# relay-attentuator-SMD.net
KiCad netlist of a schematic drawn in EAGLE
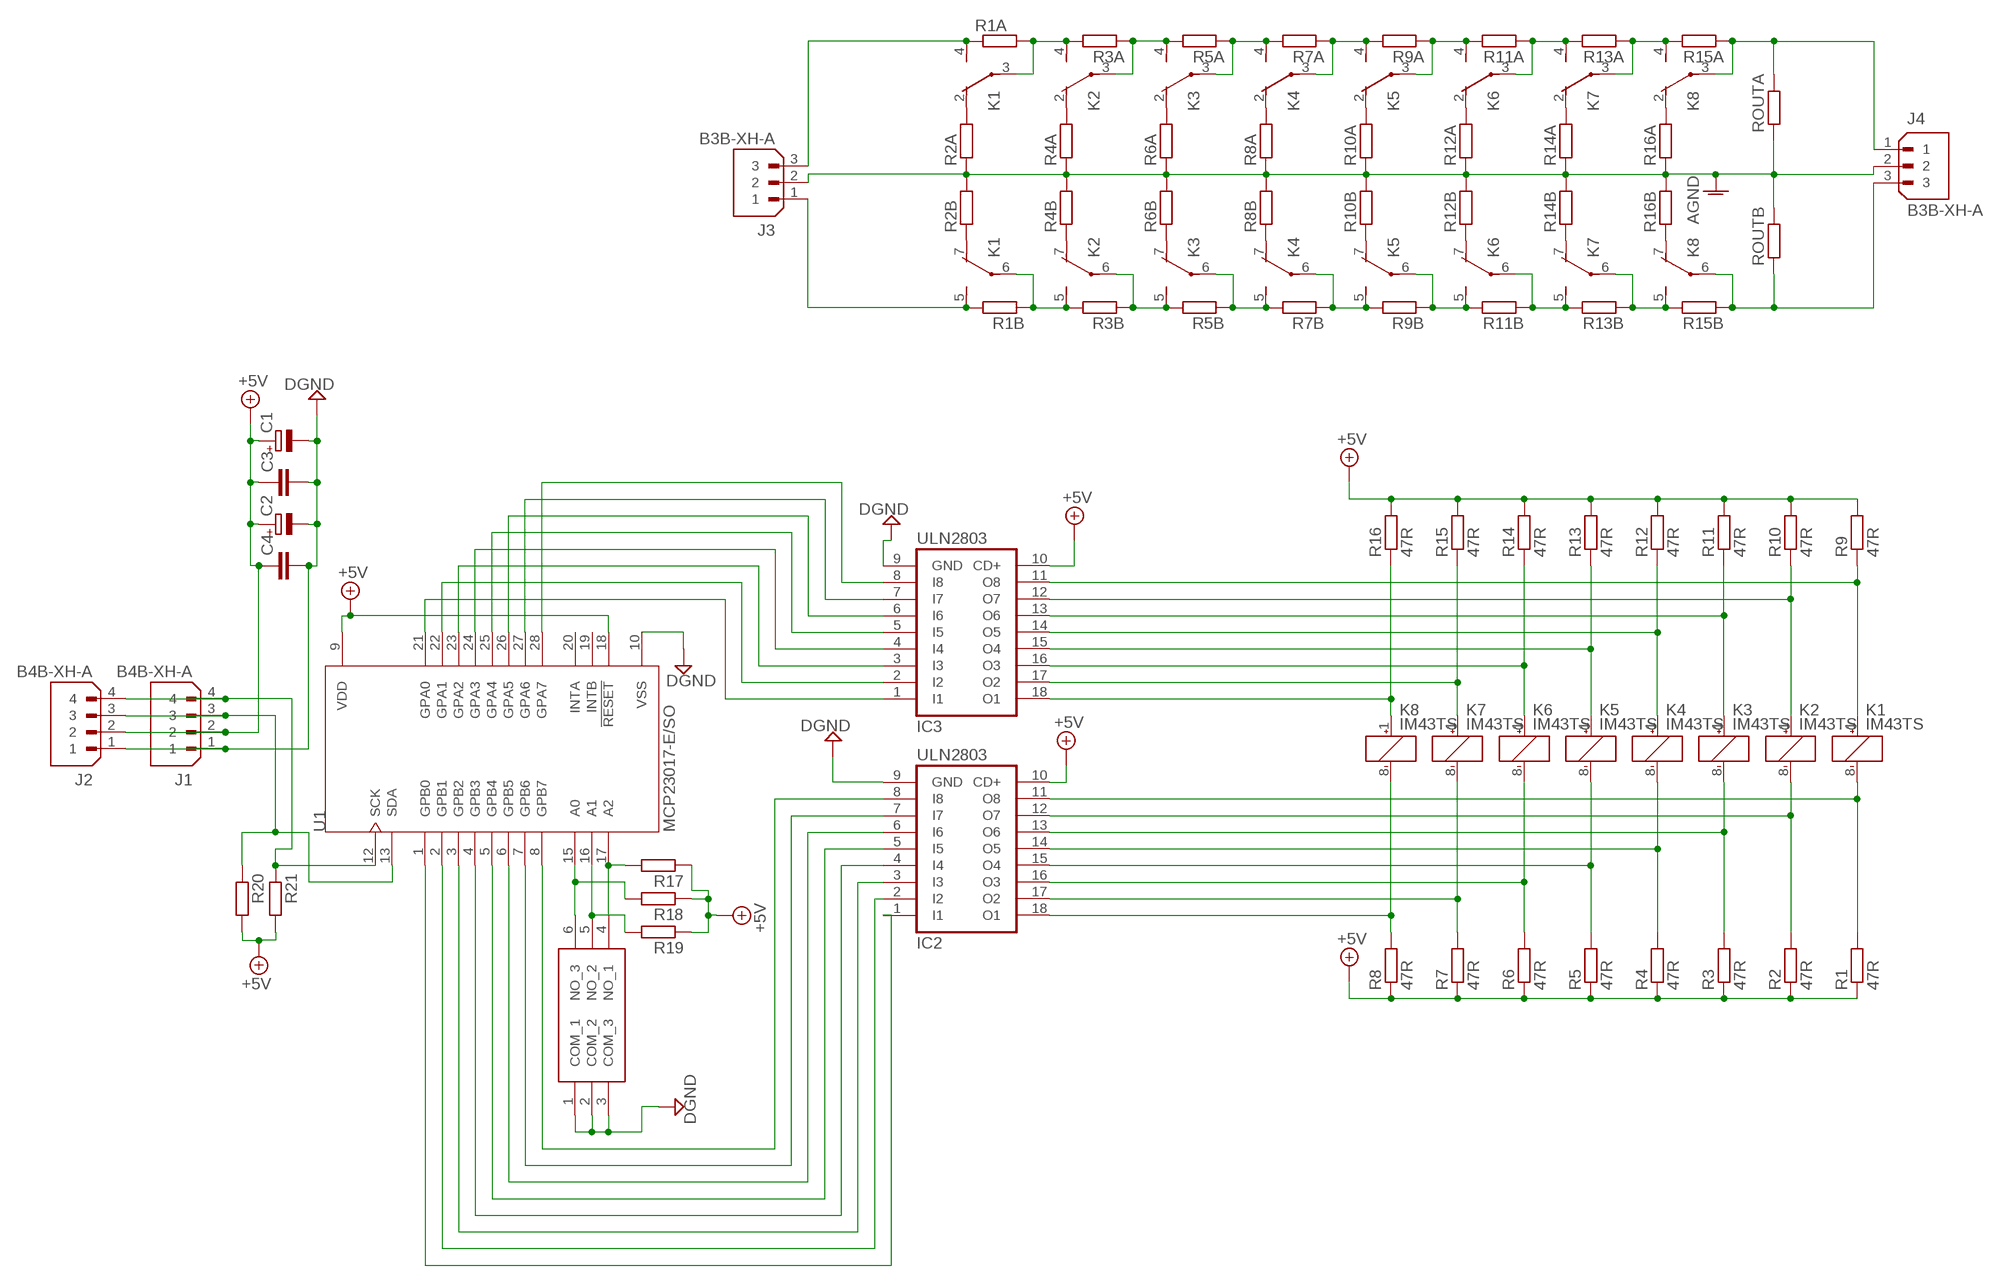
[diagram p0: schematic, sheet 1]

(export (version "E")
  (design (tool "Eeschema 10.0.6"))
  (components
    (comp (ref "C1")
      (value "CPOL-EUE3.5-8")
      (footprint "eagle-import:E3,5-8")
      (libsource (lib "eagle-import") (part "CPOL-EUE3.5-8"))
    )
    (comp (ref "C2")
      (value "CPOL-EUE3.5-8")
      (footprint "eagle-import:E3,5-8")
      (libsource (lib "eagle-import") (part "CPOL-EUE3.5-8"))
    )
    (comp (ref "C3")
      (value "C-EUC1206")
      (footprint "eagle-import:C1206")
      (libsource (lib "eagle-import") (part "C-EUC1206"))
    )
    (comp (ref "C4")
      (value "C-EUC1206")
      (footprint "eagle-import:C1206")
      (libsource (lib "eagle-import") (part "C-EUC1206"))
    )
    (comp (ref "IC2")
      (value "ULN2803")
      (footprint "eagle-import:SO-18W")
      (libsource (lib "eagle-import") (part "ULN2803ADW"))
    )
    (comp (ref "IC3")
      (value "ULN2803")
      (footprint "eagle-import:SO-18W")
      (libsource (lib "eagle-import") (part "ULN2803ADW"))
    )
    (comp (ref "J1")
      (value "B4B-XH-A")
      (footprint "eagle-import:JST_B4B-XH-A")
      (fields (field (name "MF") "JST Sales"))
      (libsource (lib "eagle-import") (part "B4B-XH-A"))
    )
    (comp (ref "J2")
      (value "B4B-XH-A")
      (footprint "eagle-import:JST_B4B-XH-A")
      (fields (field (name "MF") "JST Sales"))
      (libsource (lib "eagle-import") (part "B4B-XH-A"))
    )
    (comp (ref "J3")
      (value "B3B-XH-A")
      (footprint "eagle-import:JST_B3B-XH-A")
      (fields (field (name "MF") "JST Sales"))
      (libsource (lib "eagle-import") (part "B3B-XH-A"))
    )
    (comp (ref "J4")
      (value "B3B-XH-A")
      (footprint "eagle-import:JST_B3B-XH-A")
      (fields (field (name "MF") "JST Sales"))
      (libsource (lib "eagle-import") (part "B3B-XH-A"))
    )
    (comp (ref "K1")
      (value "IM43TS")
      (footprint "eagle-import:IM43TS")
      (libsource (lib "eagle-import") (part "IM43TS"))
    )
    (comp (ref "K2")
      (value "IM43TS")
      (footprint "eagle-import:IM43TS")
      (libsource (lib "eagle-import") (part "IM43TS"))
    )
    (comp (ref "K3")
      (value "IM43TS")
      (footprint "eagle-import:IM43TS")
      (libsource (lib "eagle-import") (part "IM43TS"))
    )
    (comp (ref "K4")
      (value "IM43TS")
      (footprint "eagle-import:IM43TS")
      (libsource (lib "eagle-import") (part "IM43TS"))
    )
    (comp (ref "K5")
      (value "IM43TS")
      (footprint "eagle-import:IM43TS")
      (libsource (lib "eagle-import") (part "IM43TS"))
    )
    (comp (ref "K6")
      (value "IM43TS")
      (footprint "eagle-import:IM43TS")
      (libsource (lib "eagle-import") (part "IM43TS"))
    )
    (comp (ref "K7")
      (value "IM43TS")
      (footprint "eagle-import:IM43TS")
      (libsource (lib "eagle-import") (part "IM43TS"))
    )
    (comp (ref "K8")
      (value "IM43TS")
      (footprint "eagle-import:IM43TS")
      (libsource (lib "eagle-import") (part "IM43TS"))
    )
    (comp (ref "R1")
      (value "47R")
      (footprint "eagle-import:R1206")
      (libsource (lib "eagle-import") (part "R-EU_R1206"))
    )
    (comp (ref "R1A")
      (value "R-EU_R1206")
      (footprint "eagle-import:R1206")
      (libsource (lib "eagle-import") (part "R-EU_R1206"))
    )
    (comp (ref "R1B")
      (value "R-EU_R1206")
      (footprint "eagle-import:R1206")
      (libsource (lib "eagle-import") (part "R-EU_R1206"))
    )
    (comp (ref "R2")
      (value "47R")
      (footprint "eagle-import:R1206")
      (libsource (lib "eagle-import") (part "R-EU_R1206"))
    )
    (comp (ref "R2A")
      (value "R-EU_R1206")
      (footprint "eagle-import:R1206")
      (libsource (lib "eagle-import") (part "R-EU_R1206"))
    )
    (comp (ref "R2B")
      (value "R-EU_R1206")
      (footprint "eagle-import:R1206")
      (libsource (lib "eagle-import") (part "R-EU_R1206"))
    )
    (comp (ref "R3")
      (value "47R")
      (footprint "eagle-import:R1206")
      (libsource (lib "eagle-import") (part "R-EU_R1206"))
    )
    (comp (ref "R3A")
      (value "R-EU_R1206")
      (footprint "eagle-import:R1206")
      (libsource (lib "eagle-import") (part "R-EU_R1206"))
    )
    (comp (ref "R3B")
      (value "R-EU_R1206")
      (footprint "eagle-import:R1206")
      (libsource (lib "eagle-import") (part "R-EU_R1206"))
    )
    (comp (ref "R4")
      (value "47R")
      (footprint "eagle-import:R1206")
      (libsource (lib "eagle-import") (part "R-EU_R1206"))
    )
    (comp (ref "R4A")
      (value "R-EU_R1206")
      (footprint "eagle-import:R1206")
      (libsource (lib "eagle-import") (part "R-EU_R1206"))
    )
    (comp (ref "R4B")
      (value "R-EU_R1206")
      (footprint "eagle-import:R1206")
      (libsource (lib "eagle-import") (part "R-EU_R1206"))
    )
    (comp (ref "R5")
      (value "47R")
      (footprint "eagle-import:R1206")
      (libsource (lib "eagle-import") (part "R-EU_R1206"))
    )
    (comp (ref "R5A")
      (value "R-EU_R1206")
      (footprint "eagle-import:R1206")
      (libsource (lib "eagle-import") (part "R-EU_R1206"))
    )
    (comp (ref "R5B")
      (value "R-EU_R1206")
      (footprint "eagle-import:R1206")
      (libsource (lib "eagle-import") (part "R-EU_R1206"))
    )
    (comp (ref "R6")
      (value "47R")
      (footprint "eagle-import:R1206")
      (libsource (lib "eagle-import") (part "R-EU_R1206"))
    )
    (comp (ref "R6A")
      (value "R-EU_R1206")
      (footprint "eagle-import:R1206")
      (libsource (lib "eagle-import") (part "R-EU_R1206"))
    )
    (comp (ref "R6B")
      (value "R-EU_R1206")
      (footprint "eagle-import:R1206")
      (libsource (lib "eagle-import") (part "R-EU_R1206"))
    )
    (comp (ref "R7")
      (value "47R")
      (footprint "eagle-import:R1206")
      (libsource (lib "eagle-import") (part "R-EU_R1206"))
    )
    (comp (ref "R7A")
      (value "R-EU_R1206")
      (footprint "eagle-import:R1206")
      (libsource (lib "eagle-import") (part "R-EU_R1206"))
    )
    (comp (ref "R7B")
      (value "R-EU_R1206")
      (footprint "eagle-import:R1206")
      (libsource (lib "eagle-import") (part "R-EU_R1206"))
    )
    (comp (ref "R8")
      (value "47R")
      (footprint "eagle-import:R1206")
      (libsource (lib "eagle-import") (part "R-EU_R1206"))
    )
    (comp (ref "R8A")
      (value "R-EU_R1206")
      (footprint "eagle-import:R1206")
      (libsource (lib "eagle-import") (part "R-EU_R1206"))
    )
    (comp (ref "R8B")
      (value "R-EU_R1206")
      (footprint "eagle-import:R1206")
      (libsource (lib "eagle-import") (part "R-EU_R1206"))
    )
    (comp (ref "R9")
      (value "47R")
      (footprint "eagle-import:R1206")
      (libsource (lib "eagle-import") (part "R-EU_R1206"))
    )
    (comp (ref "R9A")
      (value "R-EU_R1206")
      (footprint "eagle-import:R1206")
      (libsource (lib "eagle-import") (part "R-EU_R1206"))
    )
    (comp (ref "R9B")
      (value "R-EU_R1206")
      (footprint "eagle-import:R1206")
      (libsource (lib "eagle-import") (part "R-EU_R1206"))
    )
    (comp (ref "R10")
      (value "47R")
      (footprint "eagle-import:R1206")
      (libsource (lib "eagle-import") (part "R-EU_R1206"))
    )
    (comp (ref "R10A")
      (value "R-EU_R1206")
      (footprint "eagle-import:R1206")
      (libsource (lib "eagle-import") (part "R-EU_R1206"))
    )
    (comp (ref "R10B")
      (value "R-EU_R1206")
      (footprint "eagle-import:R1206")
      (libsource (lib "eagle-import") (part "R-EU_R1206"))
    )
    (comp (ref "R11")
      (value "47R")
      (footprint "eagle-import:R1206")
      (libsource (lib "eagle-import") (part "R-EU_R1206"))
    )
    (comp (ref "R11A")
      (value "R-EU_R1206")
      (footprint "eagle-import:R1206")
      (libsource (lib "eagle-import") (part "R-EU_R1206"))
    )
    (comp (ref "R11B")
      (value "R-EU_R1206")
      (footprint "eagle-import:R1206")
      (libsource (lib "eagle-import") (part "R-EU_R1206"))
    )
    (comp (ref "R12")
      (value "47R")
      (footprint "eagle-import:R1206")
      (libsource (lib "eagle-import") (part "R-EU_R1206"))
    )
    (comp (ref "R12A")
      (value "R-EU_R1206")
      (footprint "eagle-import:R1206")
      (libsource (lib "eagle-import") (part "R-EU_R1206"))
    )
    (comp (ref "R12B")
      (value "R-EU_R1206")
      (footprint "eagle-import:R1206")
      (libsource (lib "eagle-import") (part "R-EU_R1206"))
    )
    (comp (ref "R13")
      (value "47R")
      (footprint "eagle-import:R1206")
      (libsource (lib "eagle-import") (part "R-EU_R1206"))
    )
    (comp (ref "R13A")
      (value "R-EU_R1206")
      (footprint "eagle-import:R1206")
      (libsource (lib "eagle-import") (part "R-EU_R1206"))
    )
    (comp (ref "R13B")
      (value "R-EU_R1206")
      (footprint "eagle-import:R1206")
      (libsource (lib "eagle-import") (part "R-EU_R1206"))
    )
    (comp (ref "R14")
      (value "47R")
      (footprint "eagle-import:R1206")
      (libsource (lib "eagle-import") (part "R-EU_R1206"))
    )
    (comp (ref "R14A")
      (value "R-EU_R1206")
      (footprint "eagle-import:R1206")
      (libsource (lib "eagle-import") (part "R-EU_R1206"))
    )
    (comp (ref "R14B")
      (value "R-EU_R1206")
      (footprint "eagle-import:R1206")
      (libsource (lib "eagle-import") (part "R-EU_R1206"))
    )
    (comp (ref "R15")
      (value "47R")
      (footprint "eagle-import:R1206")
      (libsource (lib "eagle-import") (part "R-EU_R1206"))
    )
    (comp (ref "R15A")
      (value "R-EU_R1206")
      (footprint "eagle-import:R1206")
      (libsource (lib "eagle-import") (part "R-EU_R1206"))
    )
    (comp (ref "R15B")
      (value "R-EU_R1206")
      (footprint "eagle-import:R1206")
      (libsource (lib "eagle-import") (part "R-EU_R1206"))
    )
    (comp (ref "R16")
      (value "47R")
      (footprint "eagle-import:R1206")
      (libsource (lib "eagle-import") (part "R-EU_R1206"))
    )
    (comp (ref "R16A")
      (value "R-EU_R1206")
      (footprint "eagle-import:R1206")
      (libsource (lib "eagle-import") (part "R-EU_R1206"))
    )
    (comp (ref "R16B")
      (value "R-EU_R1206")
      (footprint "eagle-import:R1206")
      (libsource (lib "eagle-import") (part "R-EU_R1206"))
    )
    (comp (ref "R17")
      (value "47R")
      (footprint "eagle-import:R1206")
      (libsource (lib "eagle-import") (part "R-EU_R1206"))
    )
    (comp (ref "R18")
      (value "47R")
      (footprint "eagle-import:R1206")
      (libsource (lib "eagle-import") (part "R-EU_R1206"))
    )
    (comp (ref "R19")
      (value "47R")
      (footprint "eagle-import:R1206")
      (libsource (lib "eagle-import") (part "R-EU_R1206"))
    )
    (comp (ref "R20")
      (value "47R")
      (footprint "eagle-import:R1206")
      (libsource (lib "eagle-import") (part "R-EU_R1206"))
    )
    (comp (ref "R21")
      (value "47R")
      (footprint "eagle-import:R1206")
      (libsource (lib "eagle-import") (part "R-EU_R1206"))
    )
    (comp (ref "ROUTA")
      (value "R-EU_R1206")
      (footprint "eagle-import:R1206")
      (libsource (lib "eagle-import") (part "R-EU_R1206"))
    )
    (comp (ref "ROUTB")
      (value "R-EU_R1206")
      (footprint "eagle-import:R1206")
      (libsource (lib "eagle-import") (part "R-EU_R1206"))
    )
    (comp (ref "S1")
      (value "2454982-2")
      (footprint "eagle-import:24549822")
      (fields (field (name "MOUSER_PART_NUMBER") "655-2454982-2"))
      (libsource (lib "eagle-import") (part "2454982-2"))
    )
    (comp (ref "U1")
      (value "MCP23017-E/SO")
      (footprint "eagle-import:SOIC127P1030X265-28N")
      (fields (field (name "MF") "Microchip"))
      (libsource (lib "eagle-import") (part "MCP23017-E/SO"))
    )
  )
  (nets
    (net (code "1") (name "+5V") (class "Default")
      (node (ref "C1") (pin "+") (pinfunction "+_+") (pintype "passive"))
      (node (ref "C2") (pin "+") (pinfunction "+_+") (pintype "passive"))
      (node (ref "C3") (pin "1") (pinfunction "1_1") (pintype "passive"))
      (node (ref "C4") (pin "1") (pinfunction "1_1") (pintype "passive"))
      (node (ref "IC2") (pin "10") (pinfunction "CD+_10") (pintype "passive"))
      (node (ref "IC3") (pin "10") (pinfunction "CD+_10") (pintype "passive"))
      (node (ref "J1") (pin "2") (pinfunction "2_2") (pintype "passive"))
      (node (ref "J2") (pin "2") (pinfunction "2_2") (pintype "passive"))
      (node (ref "R1") (pin "1") (pinfunction "1_1") (pintype "passive"))
      (node (ref "R10") (pin "2") (pinfunction "2_2") (pintype "passive"))
      (node (ref "R11") (pin "2") (pinfunction "2_2") (pintype "passive"))
      (node (ref "R12") (pin "2") (pinfunction "2_2") (pintype "passive"))
      (node (ref "R13") (pin "2") (pinfunction "2_2") (pintype "passive"))
      (node (ref "R14") (pin "2") (pinfunction "2_2") (pintype "passive"))
      (node (ref "R15") (pin "2") (pinfunction "2_2") (pintype "passive"))
      (node (ref "R16") (pin "2") (pinfunction "2_2") (pintype "passive"))
      (node (ref "R17") (pin "1") (pinfunction "1_1") (pintype "passive"))
      (node (ref "R18") (pin "1") (pinfunction "1_1") (pintype "passive"))
      (node (ref "R19") (pin "1") (pinfunction "1_1") (pintype "passive"))
      (node (ref "R2") (pin "1") (pinfunction "1_1") (pintype "passive"))
      (node (ref "R20") (pin "2") (pinfunction "2_2") (pintype "passive"))
      (node (ref "R21") (pin "2") (pinfunction "2_2") (pintype "passive"))
      (node (ref "R3") (pin "1") (pinfunction "1_1") (pintype "passive"))
      (node (ref "R4") (pin "1") (pinfunction "1_1") (pintype "passive"))
      (node (ref "R5") (pin "1") (pinfunction "1_1") (pintype "passive"))
      (node (ref "R6") (pin "1") (pinfunction "1_1") (pintype "passive"))
      (node (ref "R7") (pin "1") (pinfunction "1_1") (pintype "passive"))
      (node (ref "R8") (pin "1") (pinfunction "1_1") (pintype "passive"))
      (node (ref "R9") (pin "2") (pinfunction "2_2") (pintype "passive"))
      (node (ref "U1") (pin "18") (pinfunction "~{RESET}_18") (pintype "output"))
      (node (ref "U1") (pin "9") (pinfunction "VDD_9") (pintype "power_in"))
    )
    (net (code "2") (name "AGND") (class "Default")
      (node (ref "J3") (pin "2") (pinfunction "2_2") (pintype "passive"))
      (node (ref "J4") (pin "2") (pinfunction "2_2") (pintype "passive"))
      (node (ref "R10A") (pin "1") (pinfunction "1_1") (pintype "passive"))
      (node (ref "R10B") (pin "2") (pinfunction "2_2") (pintype "passive"))
      (node (ref "R12A") (pin "1") (pinfunction "1_1") (pintype "passive"))
      (node (ref "R12B") (pin "2") (pinfunction "2_2") (pintype "passive"))
      (node (ref "R14A") (pin "1") (pinfunction "1_1") (pintype "passive"))
      (node (ref "R14B") (pin "2") (pinfunction "2_2") (pintype "passive"))
      (node (ref "R16A") (pin "1") (pinfunction "1_1") (pintype "passive"))
      (node (ref "R16B") (pin "2") (pinfunction "2_2") (pintype "passive"))
      (node (ref "R2A") (pin "1") (pinfunction "1_1") (pintype "passive"))
      (node (ref "R2B") (pin "2") (pinfunction "2_2") (pintype "passive"))
      (node (ref "R4A") (pin "1") (pinfunction "1_1") (pintype "passive"))
      (node (ref "R4B") (pin "2") (pinfunction "2_2") (pintype "passive"))
      (node (ref "R6A") (pin "1") (pinfunction "1_1") (pintype "passive"))
      (node (ref "R6B") (pin "2") (pinfunction "2_2") (pintype "passive"))
      (node (ref "R8A") (pin "1") (pinfunction "1_1") (pintype "passive"))
      (node (ref "R8B") (pin "2") (pinfunction "2_2") (pintype "passive"))
      (node (ref "ROUTA") (pin "1") (pinfunction "1_1") (pintype "passive"))
      (node (ref "ROUTB") (pin "2") (pinfunction "2_2") (pintype "passive"))
    )
    (net (code "3") (name "DGND") (class "Default")
      (node (ref "C1") (pin "-") (pinfunction "-_-") (pintype "passive"))
      (node (ref "C2") (pin "-") (pinfunction "-_-") (pintype "passive"))
      (node (ref "C3") (pin "2") (pinfunction "2_2") (pintype "passive"))
      (node (ref "C4") (pin "2") (pinfunction "2_2") (pintype "passive"))
      (node (ref "IC2") (pin "9") (pinfunction "GND_9") (pintype "power_in"))
      (node (ref "IC3") (pin "9") (pinfunction "GND_9") (pintype "power_in"))
      (node (ref "J1") (pin "1") (pinfunction "1_1") (pintype "passive"))
      (node (ref "J2") (pin "1") (pinfunction "1_1") (pintype "passive"))
      (node (ref "S1") (pin "1") (pinfunction "COM_1_1") (pintype "bidirectional"))
      (node (ref "S1") (pin "2") (pinfunction "COM_2_2") (pintype "bidirectional"))
      (node (ref "S1") (pin "3") (pinfunction "COM_3_3") (pintype "bidirectional"))
      (node (ref "U1") (pin "10") (pinfunction "VSS_10") (pintype "power_in"))
    )
    (net (code "4") (name "Net-(IC2-I1)") (class "Default")
      (node (ref "IC2") (pin "1") (pinfunction "I1_1") (pintype "input"))
      (node (ref "U1") (pin "1") (pinfunction "GPB0_1") (pintype "bidirectional"))
    )
    (net (code "5") (name "Net-(IC2-I2)") (class "Default")
      (node (ref "IC2") (pin "2") (pinfunction "I2_2") (pintype "input"))
      (node (ref "U1") (pin "2") (pinfunction "GPB1_2") (pintype "bidirectional"))
    )
    (net (code "6") (name "Net-(IC2-I3)") (class "Default")
      (node (ref "IC2") (pin "3") (pinfunction "I3_3") (pintype "input"))
      (node (ref "U1") (pin "3") (pinfunction "GPB2_3") (pintype "bidirectional"))
    )
    (net (code "7") (name "Net-(IC2-I4)") (class "Default")
      (node (ref "IC2") (pin "4") (pinfunction "I4_4") (pintype "input"))
      (node (ref "U1") (pin "4") (pinfunction "GPB3_4") (pintype "bidirectional"))
    )
    (net (code "8") (name "Net-(IC2-I5)") (class "Default")
      (node (ref "IC2") (pin "5") (pinfunction "I5_5") (pintype "input"))
      (node (ref "U1") (pin "5") (pinfunction "GPB4_5") (pintype "bidirectional"))
    )
    (net (code "9") (name "Net-(IC2-I6)") (class "Default")
      (node (ref "IC2") (pin "6") (pinfunction "I6_6") (pintype "input"))
      (node (ref "U1") (pin "6") (pinfunction "GPB5_6") (pintype "bidirectional"))
    )
    (net (code "10") (name "Net-(IC2-I7)") (class "Default")
      (node (ref "IC2") (pin "7") (pinfunction "I7_7") (pintype "input"))
      (node (ref "U1") (pin "7") (pinfunction "GPB6_7") (pintype "bidirectional"))
    )
    (net (code "11") (name "Net-(IC2-I8)") (class "Default")
      (node (ref "IC2") (pin "8") (pinfunction "I8_8") (pintype "input"))
      (node (ref "U1") (pin "8") (pinfunction "GPB7_8") (pintype "bidirectional"))
    )
    (net (code "12") (name "Net-(IC2-O1)") (class "Default")
      (node (ref "IC2") (pin "18") (pinfunction "O1_18") (pintype "open_collector"))
      (node (ref "K8") (pin "8") (pinfunction "-_8") (pintype "passive"))
      (node (ref "R8") (pin "2") (pinfunction "2_2") (pintype "passive"))
    )
    (net (code "13") (name "Net-(IC2-O2)") (class "Default")
      (node (ref "IC2") (pin "17") (pinfunction "O2_17") (pintype "open_collector"))
      (node (ref "K7") (pin "8") (pinfunction "-_8") (pintype "passive"))
      (node (ref "R7") (pin "2") (pinfunction "2_2") (pintype "passive"))
    )
    (net (code "14") (name "Net-(IC2-O3)") (class "Default")
      (node (ref "IC2") (pin "16") (pinfunction "O3_16") (pintype "open_collector"))
      (node (ref "K6") (pin "8") (pinfunction "-_8") (pintype "passive"))
      (node (ref "R6") (pin "2") (pinfunction "2_2") (pintype "passive"))
    )
    (net (code "15") (name "Net-(IC2-O4)") (class "Default")
      (node (ref "IC2") (pin "15") (pinfunction "O4_15") (pintype "open_collector"))
      (node (ref "K5") (pin "8") (pinfunction "-_8") (pintype "passive"))
      (node (ref "R5") (pin "2") (pinfunction "2_2") (pintype "passive"))
    )
    (net (code "16") (name "Net-(IC2-O5)") (class "Default")
      (node (ref "IC2") (pin "14") (pinfunction "O5_14") (pintype "open_collector"))
      (node (ref "K4") (pin "8") (pinfunction "-_8") (pintype "passive"))
      (node (ref "R4") (pin "2") (pinfunction "2_2") (pintype "passive"))
    )
    (net (code "17") (name "Net-(IC2-O6)") (class "Default")
      (node (ref "IC2") (pin "13") (pinfunction "O6_13") (pintype "open_collector"))
      (node (ref "K3") (pin "8") (pinfunction "-_8") (pintype "passive"))
      (node (ref "R3") (pin "2") (pinfunction "2_2") (pintype "passive"))
    )
    (net (code "18") (name "Net-(IC2-O7)") (class "Default")
      (node (ref "IC2") (pin "12") (pinfunction "O7_12") (pintype "open_collector"))
      (node (ref "K2") (pin "8") (pinfunction "-_8") (pintype "passive"))
      (node (ref "R2") (pin "2") (pinfunction "2_2") (pintype "passive"))
    )
    (net (code "19") (name "Net-(IC2-O8)") (class "Default")
      (node (ref "IC2") (pin "11") (pinfunction "O8_11") (pintype "open_collector"))
      (node (ref "K1") (pin "8") (pinfunction "-_8") (pintype "passive"))
      (node (ref "R1") (pin "2") (pinfunction "2_2") (pintype "passive"))
    )
    (net (code "20") (name "Net-(IC3-I1)") (class "Default")
      (node (ref "IC3") (pin "1") (pinfunction "I1_1") (pintype "input"))
      (node (ref "U1") (pin "21") (pinfunction "GPA0_21") (pintype "bidirectional"))
    )
    (net (code "21") (name "Net-(IC3-I2)") (class "Default")
      (node (ref "IC3") (pin "2") (pinfunction "I2_2") (pintype "input"))
      (node (ref "U1") (pin "22") (pinfunction "GPA1_22") (pintype "bidirectional"))
    )
    (net (code "22") (name "Net-(IC3-I3)") (class "Default")
      (node (ref "IC3") (pin "3") (pinfunction "I3_3") (pintype "input"))
      (node (ref "U1") (pin "23") (pinfunction "GPA2_23") (pintype "bidirectional"))
    )
    (net (code "23") (name "Net-(IC3-I4)") (class "Default")
      (node (ref "IC3") (pin "4") (pinfunction "I4_4") (pintype "input"))
      (node (ref "U1") (pin "24") (pinfunction "GPA3_24") (pintype "bidirectional"))
    )
    (net (code "24") (name "Net-(IC3-I5)") (class "Default")
      (node (ref "IC3") (pin "5") (pinfunction "I5_5") (pintype "input"))
      (node (ref "U1") (pin "25") (pinfunction "GPA4_25") (pintype "bidirectional"))
    )
    (net (code "25") (name "Net-(IC3-I6)") (class "Default")
      (node (ref "IC3") (pin "6") (pinfunction "I6_6") (pintype "input"))
      (node (ref "U1") (pin "26") (pinfunction "GPA5_26") (pintype "bidirectional"))
    )
    (net (code "26") (name "Net-(IC3-I7)") (class "Default")
      (node (ref "IC3") (pin "7") (pinfunction "I7_7") (pintype "input"))
      (node (ref "U1") (pin "27") (pinfunction "GPA6_27") (pintype "bidirectional"))
    )
    (net (code "27") (name "Net-(IC3-I8)") (class "Default")
      (node (ref "IC3") (pin "8") (pinfunction "I8_8") (pintype "input"))
      (node (ref "U1") (pin "28") (pinfunction "GPA7_28") (pintype "bidirectional"))
    )
    (net (code "28") (name "Net-(IC3-O1)") (class "Default")
      (node (ref "IC3") (pin "18") (pinfunction "O1_18") (pintype "open_collector"))
      (node (ref "K8") (pin "1") (pinfunction "+_1") (pintype "passive"))
      (node (ref "R16") (pin "1") (pinfunction "1_1") (pintype "passive"))
    )
    (net (code "29") (name "Net-(IC3-O2)") (class "Default")
      (node (ref "IC3") (pin "17") (pinfunction "O2_17") (pintype "open_collector"))
      (node (ref "K7") (pin "1") (pinfunction "+_1") (pintype "passive"))
      (node (ref "R15") (pin "1") (pinfunction "1_1") (pintype "passive"))
    )
    (net (code "30") (name "Net-(IC3-O3)") (class "Default")
      (node (ref "IC3") (pin "16") (pinfunction "O3_16") (pintype "open_collector"))
      (node (ref "K6") (pin "1") (pinfunction "+_1") (pintype "passive"))
      (node (ref "R14") (pin "1") (pinfunction "1_1") (pintype "passive"))
    )
    (net (code "31") (name "Net-(IC3-O4)") (class "Default")
      (node (ref "IC3") (pin "15") (pinfunction "O4_15") (pintype "open_collector"))
      (node (ref "K5") (pin "1") (pinfunction "+_1") (pintype "passive"))
      (node (ref "R13") (pin "1") (pinfunction "1_1") (pintype "passive"))
    )
    (net (code "32") (name "Net-(IC3-O5)") (class "Default")
      (node (ref "IC3") (pin "14") (pinfunction "O5_14") (pintype "open_collector"))
      (node (ref "K4") (pin "1") (pinfunction "+_1") (pintype "passive"))
      (node (ref "R12") (pin "1") (pinfunction "1_1") (pintype "passive"))
    )
    (net (code "33") (name "Net-(IC3-O6)") (class "Default")
      (node (ref "IC3") (pin "13") (pinfunction "O6_13") (pintype "open_collector"))
      (node (ref "K3") (pin "1") (pinfunction "+_1") (pintype "passive"))
      (node (ref "R11") (pin "1") (pinfunction "1_1") (pintype "passive"))
    )
    (net (code "34") (name "Net-(IC3-O7)") (class "Default")
      (node (ref "IC3") (pin "12") (pinfunction "O7_12") (pintype "open_collector"))
      (node (ref "K2") (pin "1") (pinfunction "+_1") (pintype "passive"))
      (node (ref "R10") (pin "1") (pinfunction "1_1") (pintype "passive"))
    )
    (net (code "35") (name "Net-(IC3-O8)") (class "Default")
      (node (ref "IC3") (pin "11") (pinfunction "O8_11") (pintype "open_collector"))
      (node (ref "K1") (pin "1") (pinfunction "+_1") (pintype "passive"))
      (node (ref "R9") (pin "1") (pinfunction "1_1") (pintype "passive"))
    )
    (net (code "36") (name "Net-(K1B-O)") (class "Default")
      (node (ref "K1") (pin "2") (pinfunction "O_2") (pintype "passive"))
      (node (ref "R2A") (pin "2") (pinfunction "2_2") (pintype "passive"))
    )
    (net (code "37") (name "Net-(K1B-P)") (class "Default")
      (node (ref "K1") (pin "3") (pinfunction "P_3") (pintype "passive"))
      (node (ref "K2") (pin "4") (pinfunction "S_4") (pintype "passive"))
      (node (ref "R1A") (pin "2") (pinfunction "2_2") (pintype "passive"))
      (node (ref "R3A") (pin "2") (pinfunction "2_2") (pintype "passive"))
    )
    (net (code "38") (name "Net-(K1B-S)") (class "Default")
      (node (ref "J3") (pin "3") (pinfunction "3_3") (pintype "passive"))
      (node (ref "K1") (pin "4") (pinfunction "S_4") (pintype "passive"))
      (node (ref "R1A") (pin "1") (pinfunction "1_1") (pintype "passive"))
    )
    (net (code "39") (name "Net-(K1C-O)") (class "Default")
      (node (ref "K1") (pin "7") (pinfunction "O_7") (pintype "passive"))
      (node (ref "R2B") (pin "1") (pinfunction "1_1") (pintype "passive"))
    )
    (net (code "40") (name "Net-(K1C-P)") (class "Default")
      (node (ref "K1") (pin "6") (pinfunction "P_6") (pintype "passive"))
      (node (ref "K2") (pin "5") (pinfunction "S_5") (pintype "passive"))
      (node (ref "R1B") (pin "1") (pinfunction "1_1") (pintype "passive"))
      (node (ref "R3B") (pin "2") (pinfunction "2_2") (pintype "passive"))
    )
    (net (code "41") (name "Net-(K1C-S)") (class "Default")
      (node (ref "J3") (pin "1") (pinfunction "1_1") (pintype "passive"))
      (node (ref "K1") (pin "5") (pinfunction "S_5") (pintype "passive"))
      (node (ref "R1B") (pin "2") (pinfunction "2_2") (pintype "passive"))
    )
    (net (code "42") (name "Net-(K2B-O)") (class "Default")
      (node (ref "K2") (pin "2") (pinfunction "O_2") (pintype "passive"))
      (node (ref "R4A") (pin "2") (pinfunction "2_2") (pintype "passive"))
    )
    (net (code "43") (name "Net-(K2B-P)") (class "Default")
      (node (ref "K2") (pin "3") (pinfunction "P_3") (pintype "passive"))
      (node (ref "K3") (pin "4") (pinfunction "S_4") (pintype "passive"))
      (node (ref "R3A") (pin "1") (pinfunction "1_1") (pintype "passive"))
      (node (ref "R5A") (pin "2") (pinfunction "2_2") (pintype "passive"))
    )
    (net (code "44") (name "Net-(K2C-O)") (class "Default")
      (node (ref "K2") (pin "7") (pinfunction "O_7") (pintype "passive"))
      (node (ref "R4B") (pin "1") (pinfunction "1_1") (pintype "passive"))
    )
    (net (code "45") (name "Net-(K2C-P)") (class "Default")
      (node (ref "K2") (pin "6") (pinfunction "P_6") (pintype "passive"))
      (node (ref "K3") (pin "5") (pinfunction "S_5") (pintype "passive"))
      (node (ref "R3B") (pin "1") (pinfunction "1_1") (pintype "passive"))
      (node (ref "R5B") (pin "2") (pinfunction "2_2") (pintype "passive"))
    )
    (net (code "46") (name "Net-(K3B-O)") (class "Default")
      (node (ref "K3") (pin "2") (pinfunction "O_2") (pintype "passive"))
      (node (ref "R6A") (pin "2") (pinfunction "2_2") (pintype "passive"))
    )
    (net (code "47") (name "Net-(K3B-P)") (class "Default")
      (node (ref "K3") (pin "3") (pinfunction "P_3") (pintype "passive"))
      (node (ref "K4") (pin "4") (pinfunction "S_4") (pintype "passive"))
      (node (ref "R5A") (pin "1") (pinfunction "1_1") (pintype "passive"))
      (node (ref "R7A") (pin "2") (pinfunction "2_2") (pintype "passive"))
    )
    (net (code "48") (name "Net-(K3C-O)") (class "Default")
      (node (ref "K3") (pin "7") (pinfunction "O_7") (pintype "passive"))
      (node (ref "R6B") (pin "1") (pinfunction "1_1") (pintype "passive"))
    )
    (net (code "49") (name "Net-(K3C-P)") (class "Default")
      (node (ref "K3") (pin "6") (pinfunction "P_6") (pintype "passive"))
      (node (ref "K4") (pin "5") (pinfunction "S_5") (pintype "passive"))
      (node (ref "R5B") (pin "1") (pinfunction "1_1") (pintype "passive"))
      (node (ref "R7B") (pin "2") (pinfunction "2_2") (pintype "passive"))
    )
    (net (code "50") (name "Net-(K4B-O)") (class "Default")
      (node (ref "K4") (pin "2") (pinfunction "O_2") (pintype "passive"))
      (node (ref "R8A") (pin "2") (pinfunction "2_2") (pintype "passive"))
    )
    (net (code "51") (name "Net-(K4B-P)") (class "Default")
      (node (ref "K4") (pin "3") (pinfunction "P_3") (pintype "passive"))
      (node (ref "K5") (pin "4") (pinfunction "S_4") (pintype "passive"))
      (node (ref "R7A") (pin "1") (pinfunction "1_1") (pintype "passive"))
      (node (ref "R9A") (pin "2") (pinfunction "2_2") (pintype "passive"))
    )
    (net (code "52") (name "Net-(K4C-O)") (class "Default")
      (node (ref "K4") (pin "7") (pinfunction "O_7") (pintype "passive"))
      (node (ref "R8B") (pin "1") (pinfunction "1_1") (pintype "passive"))
    )
    (net (code "53") (name "Net-(K4C-P)") (class "Default")
      (node (ref "K4") (pin "6") (pinfunction "P_6") (pintype "passive"))
      (node (ref "K5") (pin "5") (pinfunction "S_5") (pintype "passive"))
      (node (ref "R7B") (pin "1") (pinfunction "1_1") (pintype "passive"))
      (node (ref "R9B") (pin "2") (pinfunction "2_2") (pintype "passive"))
    )
    (net (code "54") (name "Net-(K5B-O)") (class "Default")
      (node (ref "K5") (pin "2") (pinfunction "O_2") (pintype "passive"))
      (node (ref "R10A") (pin "2") (pinfunction "2_2") (pintype "passive"))
    )
    (net (code "55") (name "Net-(K5B-P)") (class "Default")
      (node (ref "K5") (pin "3") (pinfunction "P_3") (pintype "passive"))
      (node (ref "K6") (pin "4") (pinfunction "S_4") (pintype "passive"))
      (node (ref "R11A") (pin "2") (pinfunction "2_2") (pintype "passive"))
      (node (ref "R9A") (pin "1") (pinfunction "1_1") (pintype "passive"))
    )
    (net (code "56") (name "Net-(K5C-O)") (class "Default")
      (node (ref "K5") (pin "7") (pinfunction "O_7") (pintype "passive"))
      (node (ref "R10B") (pin "1") (pinfunction "1_1") (pintype "passive"))
    )
    (net (code "57") (name "Net-(K5C-P)") (class "Default")
      (node (ref "K5") (pin "6") (pinfunction "P_6") (pintype "passive"))
      (node (ref "K6") (pin "5") (pinfunction "S_5") (pintype "passive"))
      (node (ref "R11B") (pin "2") (pinfunction "2_2") (pintype "passive"))
      (node (ref "R9B") (pin "1") (pinfunction "1_1") (pintype "passive"))
    )
    (net (code "58") (name "Net-(K6B-O)") (class "Default")
      (node (ref "K6") (pin "2") (pinfunction "O_2") (pintype "passive"))
      (node (ref "R12A") (pin "2") (pinfunction "2_2") (pintype "passive"))
    )
    (net (code "59") (name "Net-(K6B-P)") (class "Default")
      (node (ref "K6") (pin "3") (pinfunction "P_3") (pintype "passive"))
      (node (ref "K7") (pin "4") (pinfunction "S_4") (pintype "passive"))
      (node (ref "R11A") (pin "1") (pinfunction "1_1") (pintype "passive"))
      (node (ref "R13A") (pin "2") (pinfunction "2_2") (pintype "passive"))
    )
    (net (code "60") (name "Net-(K6C-O)") (class "Default")
      (node (ref "K6") (pin "7") (pinfunction "O_7") (pintype "passive"))
      (node (ref "R12B") (pin "1") (pinfunction "1_1") (pintype "passive"))
    )
    (net (code "61") (name "Net-(K6C-P)") (class "Default")
      (node (ref "K6") (pin "6") (pinfunction "P_6") (pintype "passive"))
      (node (ref "K7") (pin "5") (pinfunction "S_5") (pintype "passive"))
      (node (ref "R11B") (pin "1") (pinfunction "1_1") (pintype "passive"))
      (node (ref "R13B") (pin "2") (pinfunction "2_2") (pintype "passive"))
    )
    (net (code "62") (name "Net-(K7B-O)") (class "Default")
      (node (ref "K7") (pin "2") (pinfunction "O_2") (pintype "passive"))
      (node (ref "R14A") (pin "2") (pinfunction "2_2") (pintype "passive"))
    )
    (net (code "63") (name "Net-(K7B-P)") (class "Default")
      (node (ref "K7") (pin "3") (pinfunction "P_3") (pintype "passive"))
      (node (ref "K8") (pin "4") (pinfunction "S_4") (pintype "passive"))
      (node (ref "R13A") (pin "1") (pinfunction "1_1") (pintype "passive"))
      (node (ref "R15A") (pin "2") (pinfunction "2_2") (pintype "passive"))
    )
    (net (code "64") (name "Net-(K7C-O)") (class "Default")
      (node (ref "K7") (pin "7") (pinfunction "O_7") (pintype "passive"))
      (node (ref "R14B") (pin "1") (pinfunction "1_1") (pintype "passive"))
    )
    (net (code "65") (name "Net-(K7C-P)") (class "Default")
      (node (ref "K7") (pin "6") (pinfunction "P_6") (pintype "passive"))
      (node (ref "K8") (pin "5") (pinfunction "S_5") (pintype "passive"))
      (node (ref "R13B") (pin "1") (pinfunction "1_1") (pintype "passive"))
      (node (ref "R15B") (pin "2") (pinfunction "2_2") (pintype "passive"))
    )
    (net (code "66") (name "Net-(K8B-O)") (class "Default")
      (node (ref "K8") (pin "2") (pinfunction "O_2") (pintype "passive"))
      (node (ref "R16A") (pin "2") (pinfunction "2_2") (pintype "passive"))
    )
    (net (code "67") (name "Net-(K8B-P)") (class "Default")
      (node (ref "J4") (pin "1") (pinfunction "1_1") (pintype "passive"))
      (node (ref "K8") (pin "3") (pinfunction "P_3") (pintype "passive"))
      (node (ref "R15A") (pin "1") (pinfunction "1_1") (pintype "passive"))
      (node (ref "ROUTA") (pin "2") (pinfunction "2_2") (pintype "passive"))
    )
    (net (code "68") (name "Net-(K8C-O)") (class "Default")
      (node (ref "K8") (pin "7") (pinfunction "O_7") (pintype "passive"))
      (node (ref "R16B") (pin "1") (pinfunction "1_1") (pintype "passive"))
    )
    (net (code "69") (name "Net-(K8C-P)") (class "Default")
      (node (ref "J4") (pin "3") (pinfunction "3_3") (pintype "passive"))
      (node (ref "K8") (pin "6") (pinfunction "P_6") (pintype "passive"))
      (node (ref "R15B") (pin "1") (pinfunction "1_1") (pintype "passive"))
      (node (ref "ROUTB") (pin "1") (pinfunction "1_1") (pintype "passive"))
    )
    (net (code "70") (name "Net-(S1-NO_1)") (class "Default")
      (node (ref "R17") (pin "2") (pinfunction "2_2") (pintype "passive"))
      (node (ref "S1") (pin "4") (pinfunction "NO_1_4") (pintype "bidirectional"))
      (node (ref "U1") (pin "17") (pinfunction "A2_17") (pintype "input"))
    )
    (net (code "71") (name "Net-(S1-NO_2)") (class "Default")
      (node (ref "R19") (pin "2") (pinfunction "2_2") (pintype "passive"))
      (node (ref "S1") (pin "5") (pinfunction "NO_2_5") (pintype "bidirectional"))
      (node (ref "U1") (pin "16") (pinfunction "A1_16") (pintype "input"))
    )
    (net (code "72") (name "Net-(S1-NO_3)") (class "Default")
      (node (ref "R18") (pin "2") (pinfunction "2_2") (pintype "passive"))
      (node (ref "S1") (pin "6") (pinfunction "NO_3_6") (pintype "bidirectional"))
      (node (ref "U1") (pin "15") (pinfunction "A0_15") (pintype "input"))
    )
    (net (code "73") (name "Net-(U1-SCK)") (class "Default")
      (node (ref "J1") (pin "4") (pinfunction "4_4") (pintype "passive"))
      (node (ref "J2") (pin "4") (pinfunction "4_4") (pintype "passive"))
      (node (ref "R21") (pin "1") (pinfunction "1_1") (pintype "passive"))
      (node (ref "U1") (pin "12") (pinfunction "SCK_12") (pintype "input"))
    )
    (net (code "74") (name "Net-(U1-SDA)") (class "Default")
      (node (ref "J1") (pin "3") (pinfunction "3_3") (pintype "passive"))
      (node (ref "J2") (pin "3") (pinfunction "3_3") (pintype "passive"))
      (node (ref "R20") (pin "1") (pinfunction "1_1") (pintype "passive"))
      (node (ref "U1") (pin "13") (pinfunction "SDA_13") (pintype "bidirectional"))
    )
    (net (code "75") (name "unconnected-(U1-INTA-Pad20)") (class "Default")
      (node (ref "U1") (pin "20") (pinfunction "INTA_20") (pintype "output"))
    )
    (net (code "76") (name "unconnected-(U1-INTB-Pad19)") (class "Default")
      (node (ref "U1") (pin "19") (pinfunction "INTB_19") (pintype "output"))
    )
  )
)
